# SCH_RemdesKVM_2025-04-20.net
KiCad netlist of a schematic drawn in EasyEDA
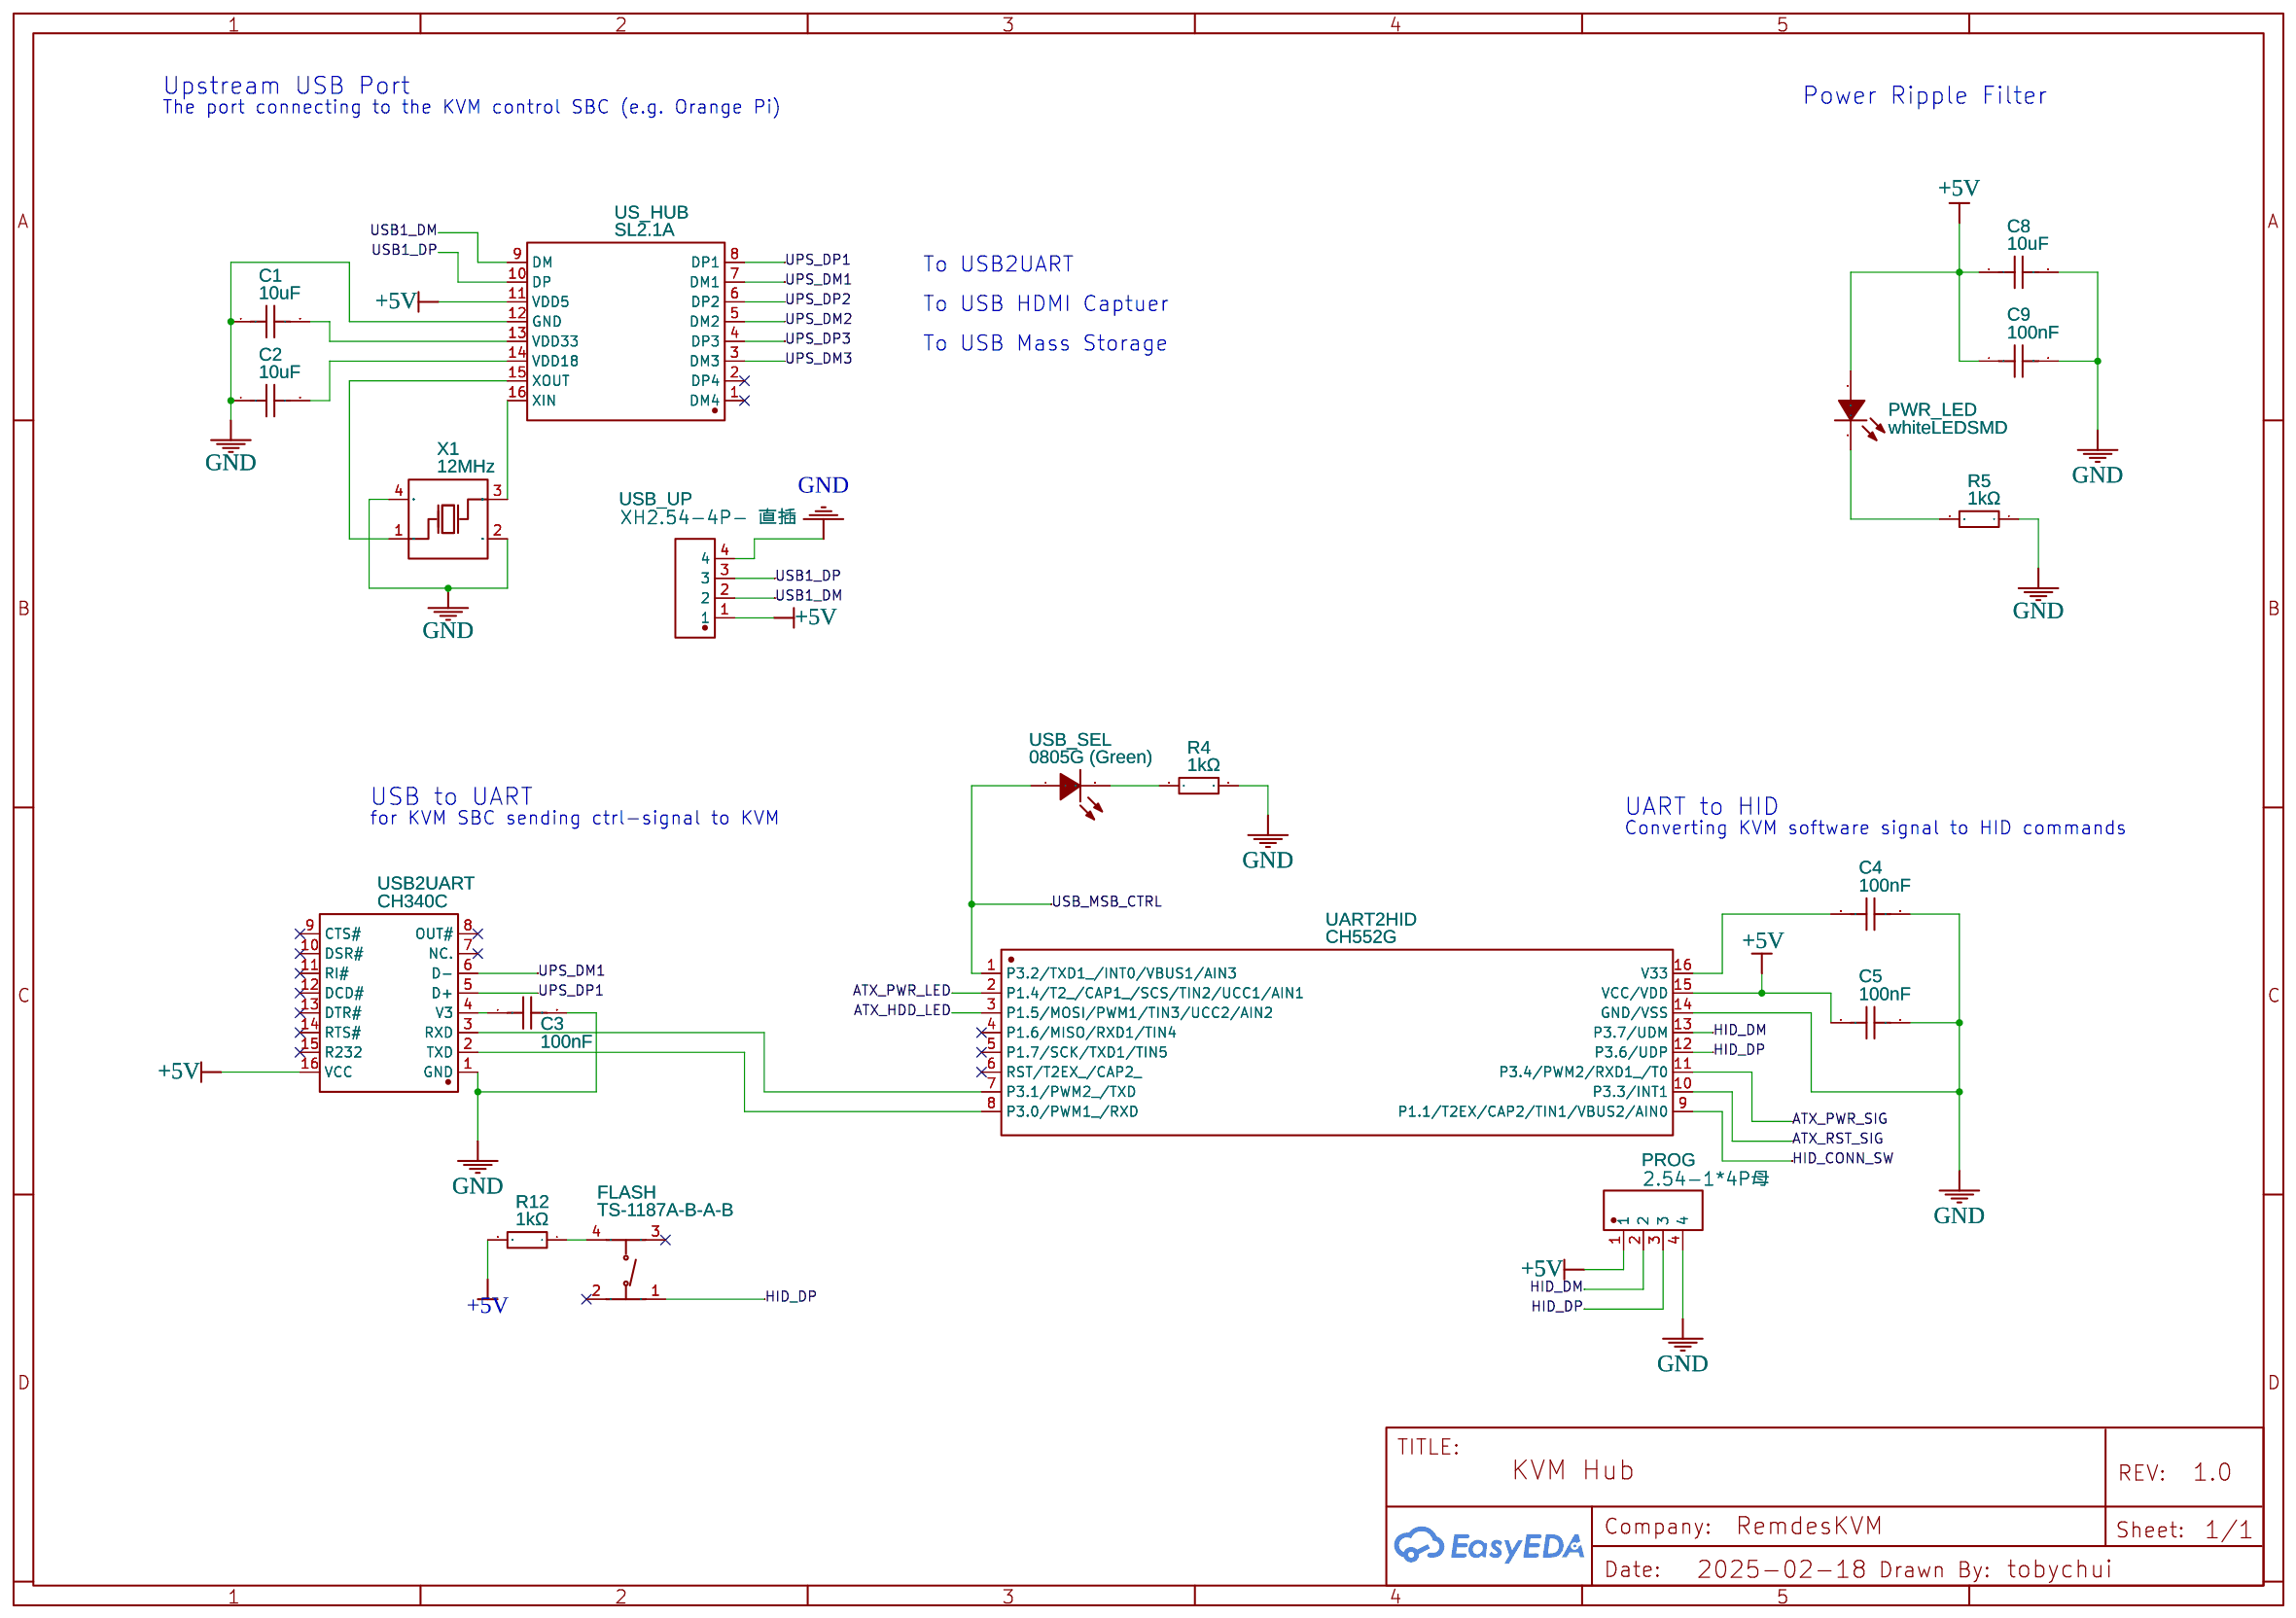
[diagram p0: KVM]
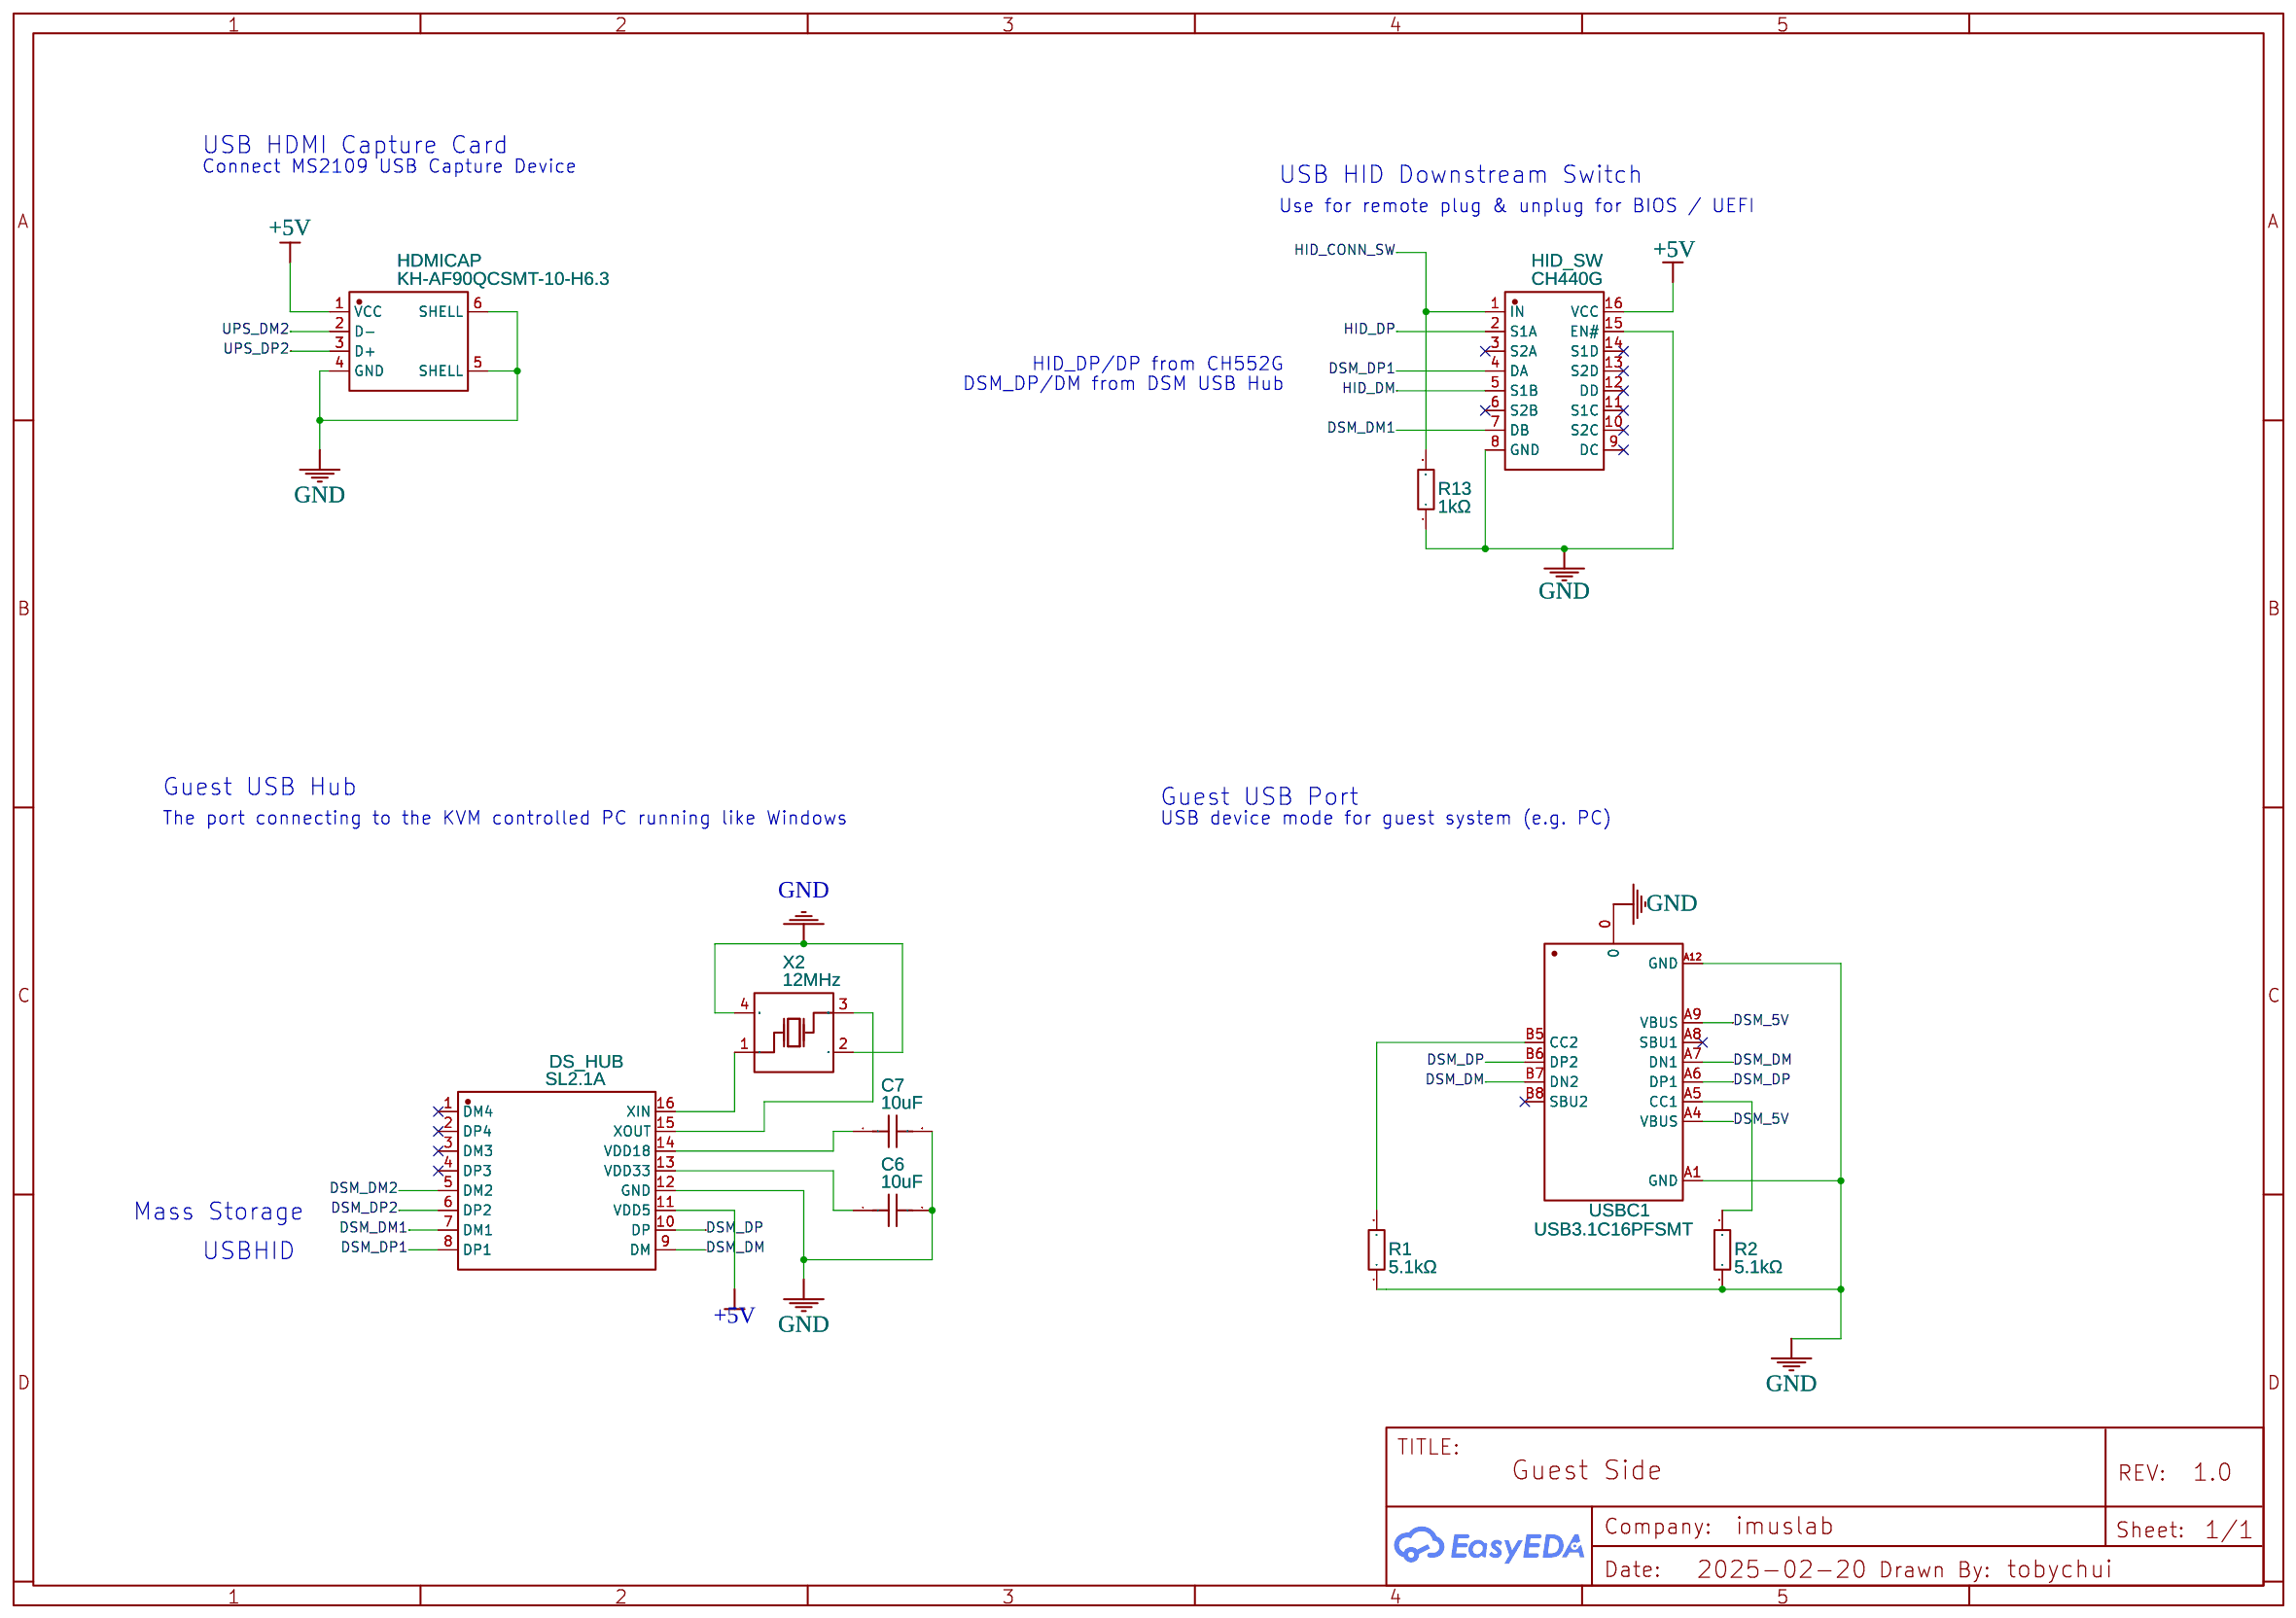
[diagram p1: Guest]
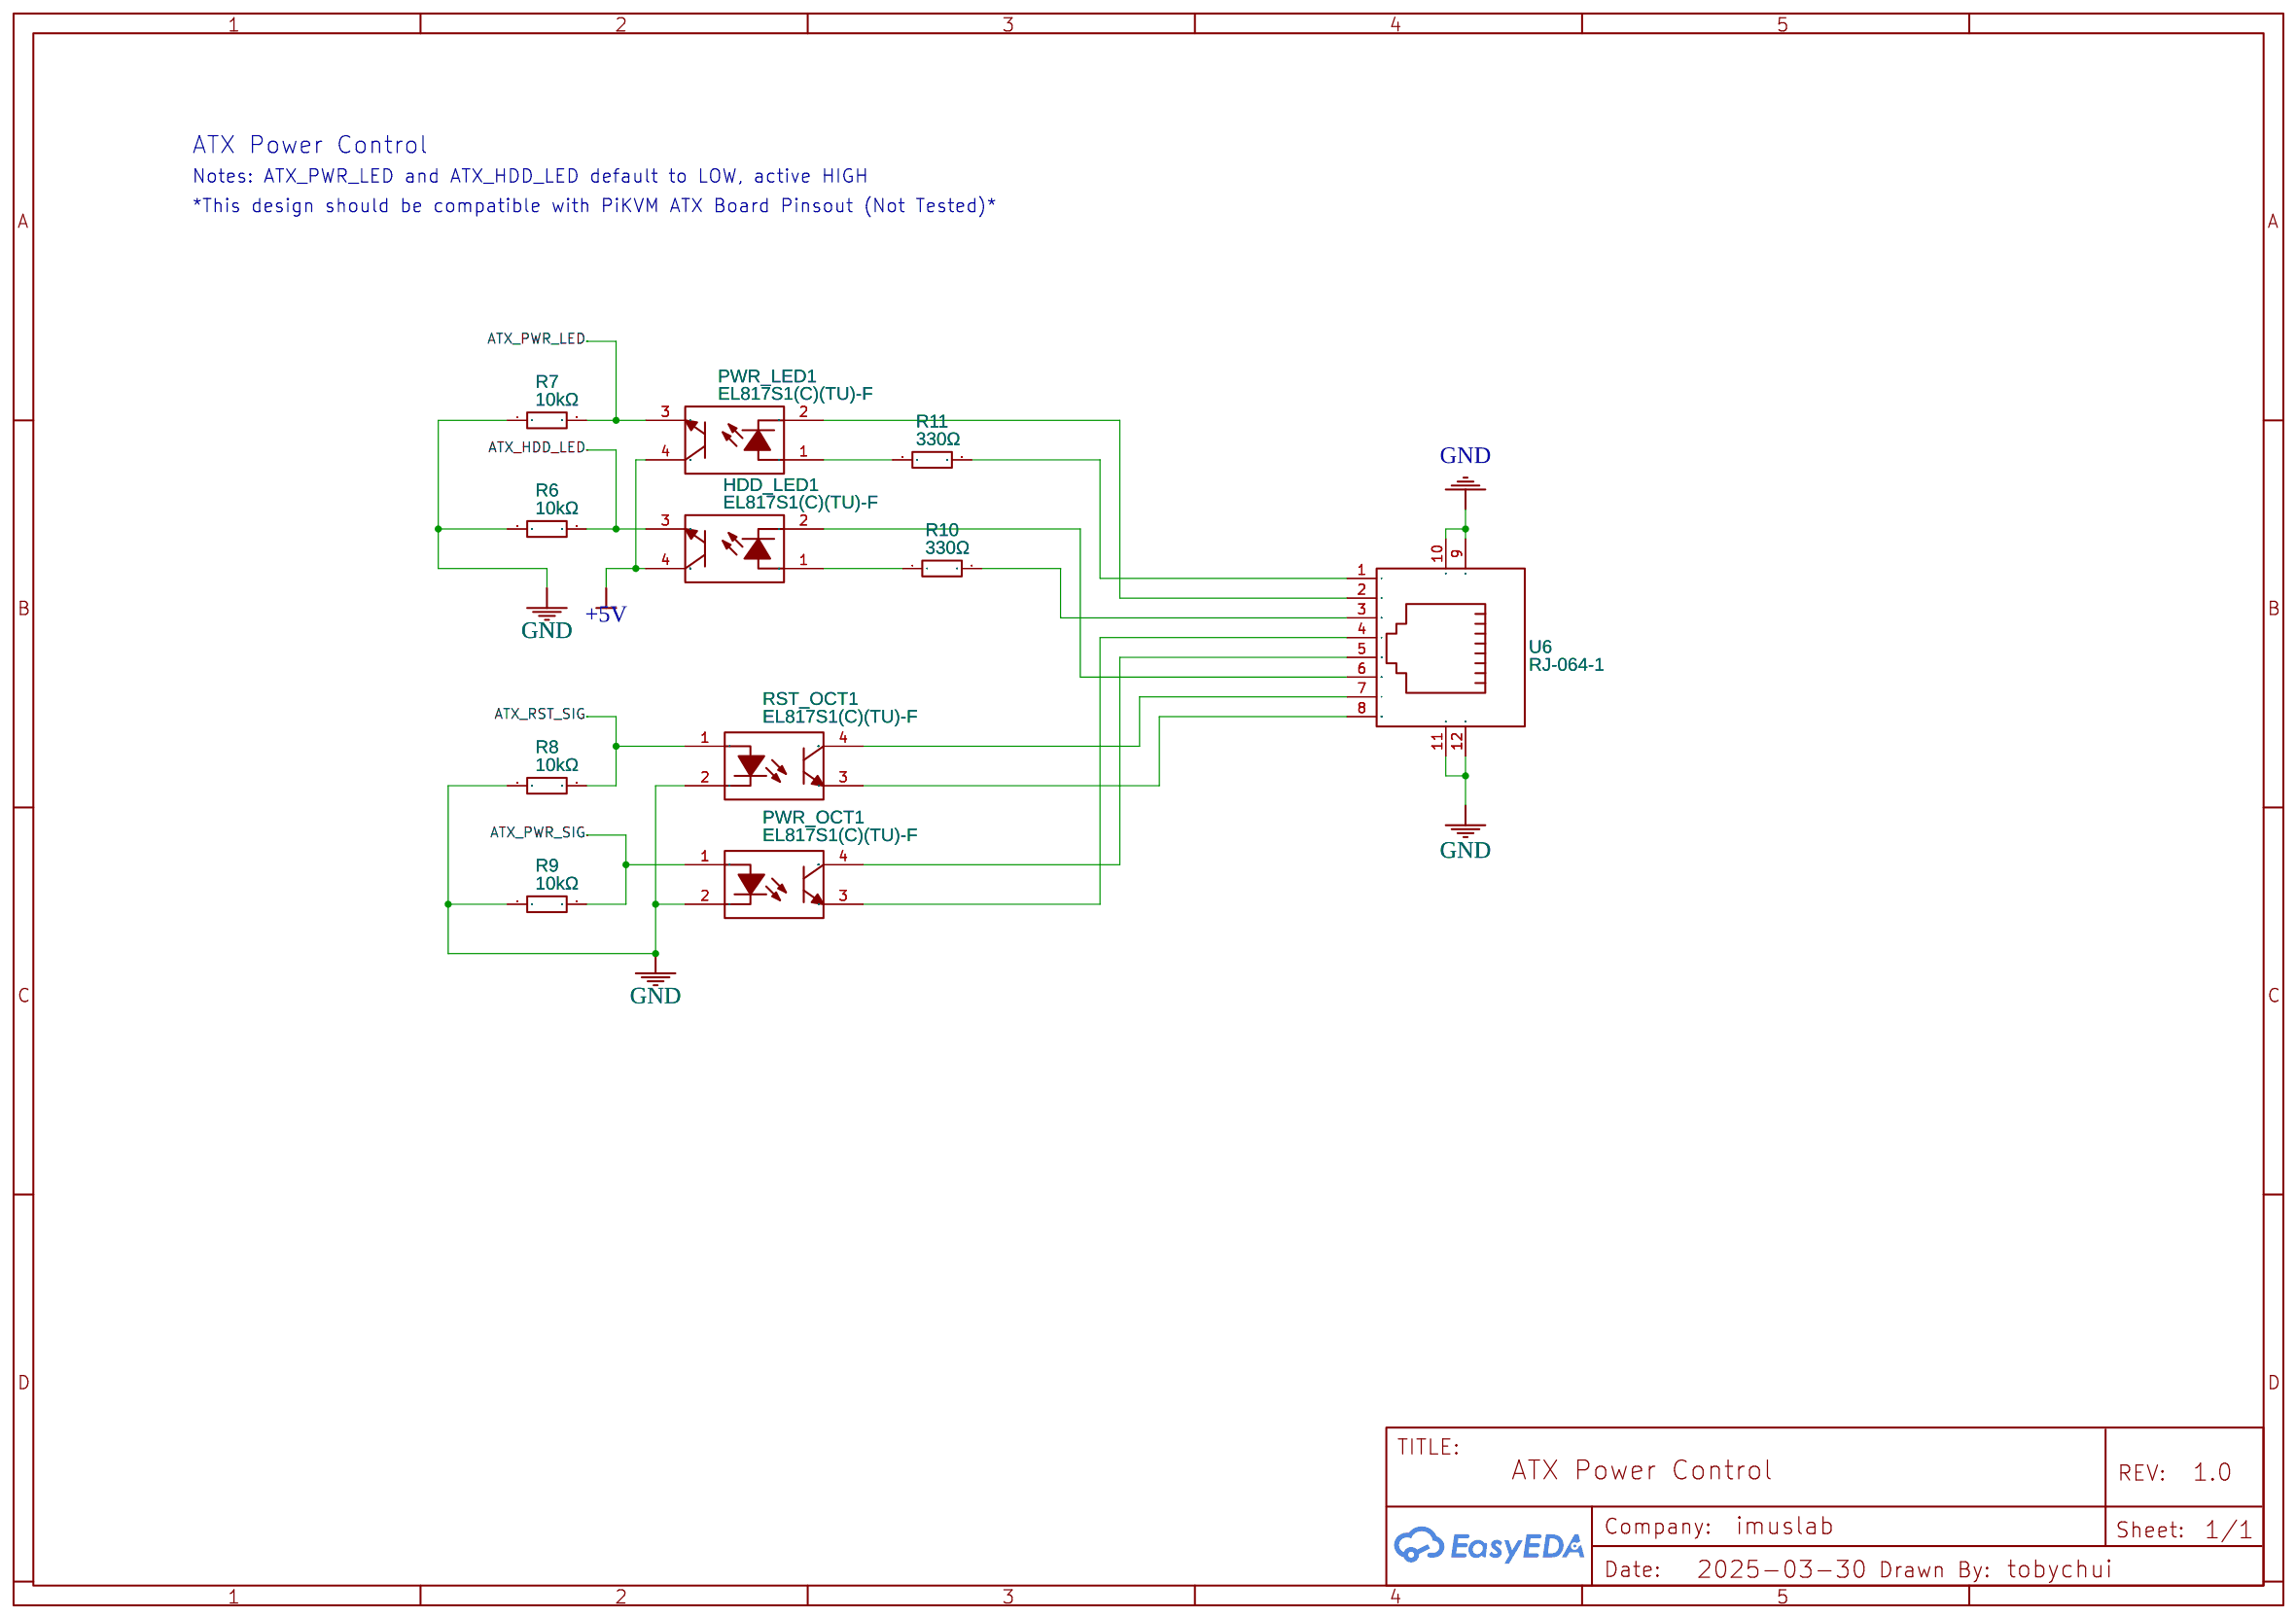
[diagram p2: ATX Power Control]
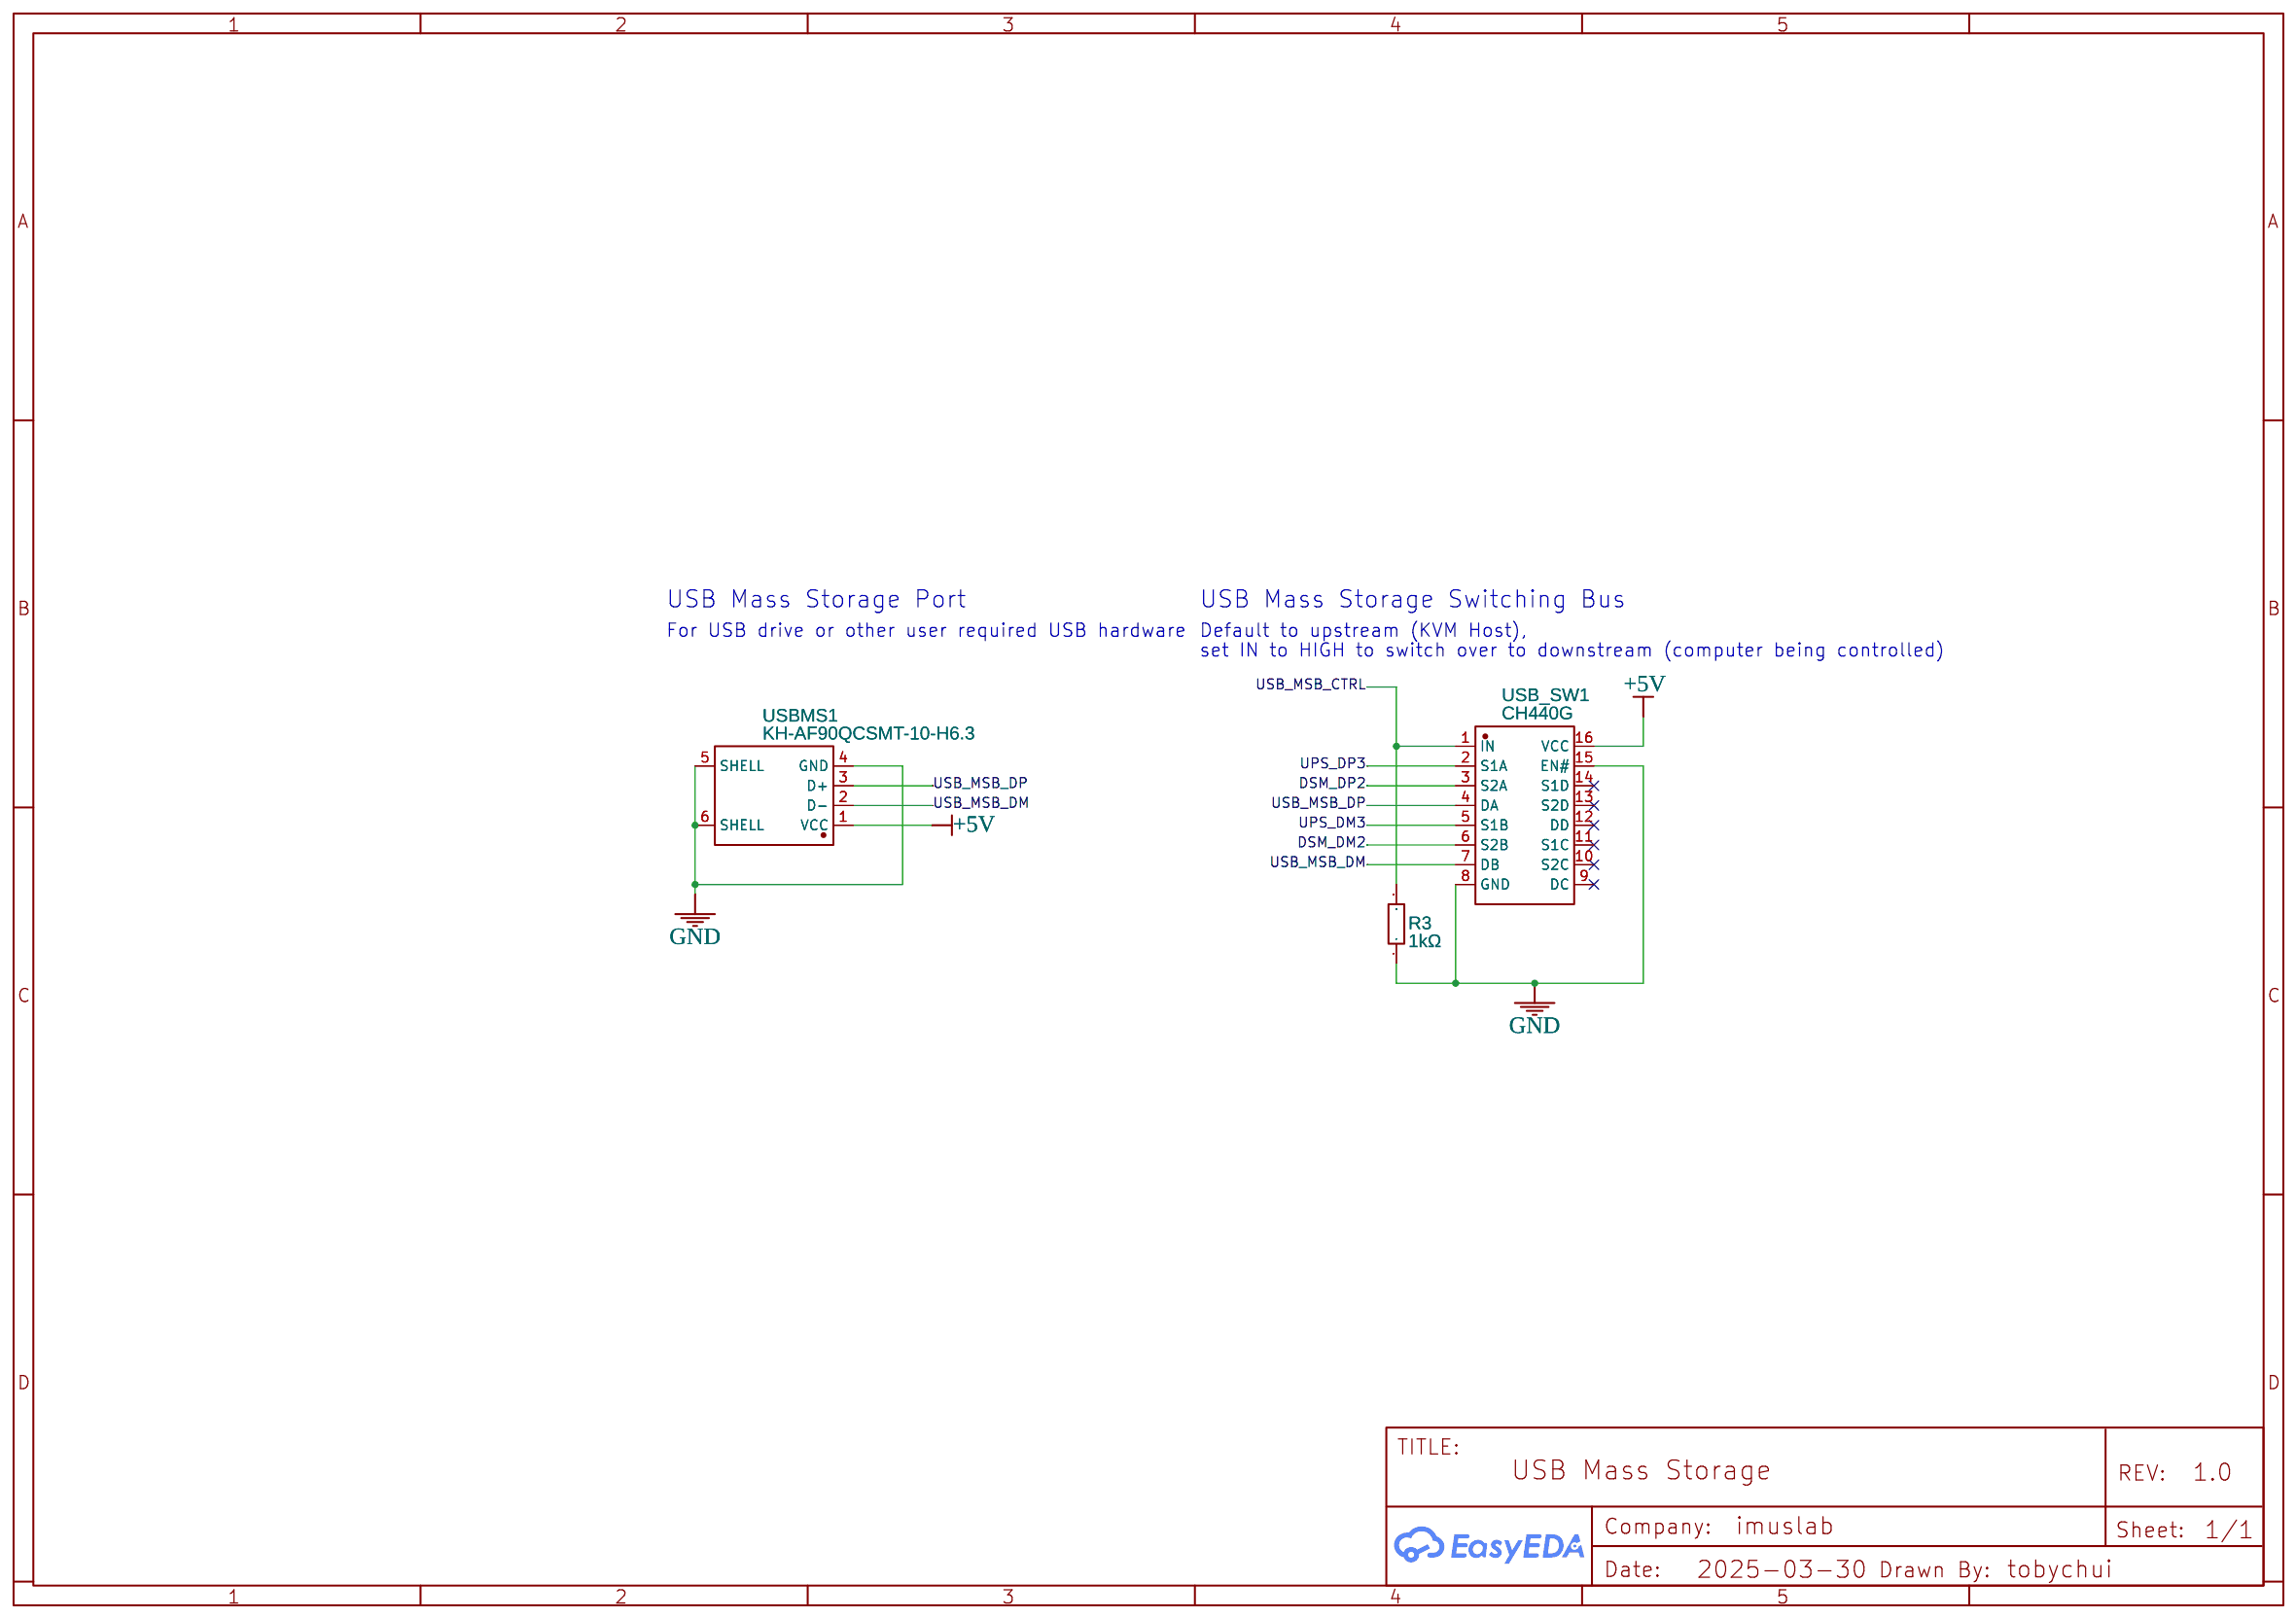
[diagram p3: USB Mass Storage]

(export (version "E")
  (design (tool "Eeschema 10.0.6"))
  (components
    (comp (ref "C1")
      (value "10uF")
      (fields
        (field (name "Manufacturer Part") "CL21A106KAYNNNE")
        (field (name "Manufacturer") "SAMSUNG(三星)")
      )
      (libsource (lib "") (part "CL21A106KAYNNNE"))
    )
    (comp (ref "C2")
      (value "10uF")
      (fields
        (field (name "Manufacturer Part") "CL21A106KAYNNNE")
        (field (name "Manufacturer") "SAMSUNG(三星)")
      )
      (libsource (lib "") (part "CL21A106KAYNNNE"))
    )
    (comp (ref "C3")
      (value "100nF")
      (fields
        (field (name "Manufacturer Part") "CC0805KRX7R9BB104")
        (field (name "Manufacturer") "YAGEO(国巨)")
      )
      (libsource (lib "") (part "CC0805KRX7R9BB104"))
    )
    (comp (ref "C4")
      (value "100nF")
      (fields
        (field (name "Manufacturer Part") "CC0805KRX7R9BB104")
        (field (name "Manufacturer") "YAGEO(国巨)")
      )
      (libsource (lib "") (part "CC0805KRX7R9BB104"))
    )
    (comp (ref "C5")
      (value "100nF")
      (fields
        (field (name "Manufacturer Part") "CC0805KRX7R9BB104")
        (field (name "Manufacturer") "YAGEO(国巨)")
      )
      (libsource (lib "") (part "CC0805KRX7R9BB104"))
    )
    (comp (ref "C8")
      (value "10uF")
      (fields
        (field (name "Manufacturer Part") "CL21A106KAYNNNE")
        (field (name "Manufacturer") "SAMSUNG(三星)")
      )
      (libsource (lib "") (part "CL21A106KAYNNNE"))
    )
    (comp (ref "C9")
      (value "100nF")
      (fields
        (field (name "Manufacturer Part") "CC0805KRX7R9BB104")
        (field (name "Manufacturer") "YAGEO(国巨)")
      )
      (libsource (lib "") (part "CC0805KRX7R9BB104"))
    )
    (comp (ref "FLASH")
      (value "TS-1187A-B-A-B")
      (fields (field (name "Manufacturer") "XKB Connectivity(中国星坤)"))
      (libsource (lib "") (part "TS-1187A-B-A-B"))
    )
    (comp (ref "PROG")
      (value "2.54-1*4P母")
      (fields (field (name "Manufacturer") "BOOMELE(博穆精密)"))
      (libsource (lib "") (part "2.54-1*4P母"))
    )
    (comp (ref "PWR_LED")
      (value "whiteLEDSMD")
      (fields (field (name "Manufacturer Part") "KT-0805W") (field (name "Manufacturer") "KENTO"))
      (libsource (lib "") (part "whiteLEDSMD"))
    )
    (comp (ref "R4")
      (value "1kΩ")
      (fields
        (field (name "Manufacturer Part") "0805W8F1001T5E")
        (field (name "Manufacturer") "UNI-ROYAL(厚声)")
      )
      (libsource (lib "") (part "0805W8F1001T5E"))
    )
    (comp (ref "R5")
      (value "1kΩ")
      (fields
        (field (name "Manufacturer Part") "0805W8F1001T5E")
        (field (name "Manufacturer") "UNI-ROYAL(厚声)")
      )
      (libsource (lib "") (part "0805W8F1001T5E"))
    )
    (comp (ref "R12")
      (value "1kΩ")
      (fields
        (field (name "Manufacturer Part") "0805W8F1001T5E")
        (field (name "Manufacturer") "UNI-ROYAL(厚声)")
      )
      (libsource (lib "") (part "0805W8F1001T5E"))
    )
    (comp (ref "UART2HID")
      (value "CH552G")
      (fields (field (name "Manufacturer") "WCH(南京沁恒)"))
      (libsource (lib "") (part "CH552G"))
    )
    (comp (ref "USB2UART")
      (value "CH340C")
      (fields (field (name "Manufacturer") "WCH(南京沁恒)"))
      (libsource (lib "") (part "CH340C"))
    )
    (comp (ref "USB_SEL")
      (value "0805G (Green)")
      (fields (field (name "Manufacturer Part") "KT-0805G") (field (name "Manufacturer") "KENTO"))
      (libsource (lib "") (part "0805G (Green)"))
    )
    (comp (ref "USB_UP") (value "XH2.54-4P- 直插") (libsource (lib "") (part "XH2.54-4P- 直插")))
    (comp (ref "US_HUB")
      (value "SL2.1A")
      (fields (field (name "Manufacturer") "CoreChips(和芯润德)"))
      (libsource (lib "") (part "SL2.1A"))
    )
    (comp (ref "X1")
      (value "12MHz")
      (fields (field (name "Manufacturer Part") "X322512MSB4SI") (field (name "Manufacturer") "YXC(扬兴晶振)"))
      (libsource (lib "") (part "X322512MSB4SI"))
    )
    (comp (ref "C6")
      (value "10uF")
      (fields
        (field (name "Manufacturer Part") "CL21A106KAYNNNE")
        (field (name "Manufacturer") "SAMSUNG(三星)")
      )
      (libsource (lib "") (part "CL21A106KAYNNNE"))
    )
    (comp (ref "C7")
      (value "10uF")
      (fields
        (field (name "Manufacturer Part") "CL21A106KAYNNNE")
        (field (name "Manufacturer") "SAMSUNG(三星)")
      )
      (libsource (lib "") (part "CL21A106KAYNNNE"))
    )
    (comp (ref "DS_HUB")
      (value "SL2.1A")
      (fields (field (name "Manufacturer") "CoreChips(和芯润德)"))
      (libsource (lib "") (part "SL2.1A"))
    )
    (comp (ref "HDMICAP")
      (value "KH-AF90QCSMT-10-H6.3")
      (fields (field (name "Manufacturer") "kinghelm(金航标)"))
      (libsource (lib "") (part "KH-AF90QCSMT-10-H6.3"))
    )
    (comp (ref "HID_SW")
      (value "CH440G")
      (fields (field (name "Manufacturer") "WCH(南京沁恒)"))
      (libsource (lib "") (part "CH440G"))
    )
    (comp (ref "R1")
      (value "5.1kΩ")
      (fields
        (field (name "Manufacturer Part") "0805W8F5101T5E")
        (field (name "Manufacturer") "UNI-ROYAL(厚声)")
      )
      (libsource (lib "") (part "0805W8F5101T5E"))
    )
    (comp (ref "R2")
      (value "5.1kΩ")
      (fields
        (field (name "Manufacturer Part") "0805W8F5101T5E")
        (field (name "Manufacturer") "UNI-ROYAL(厚声)")
      )
      (libsource (lib "") (part "0805W8F5101T5E"))
    )
    (comp (ref "R13")
      (value "1kΩ")
      (fields
        (field (name "Manufacturer Part") "0805W8F1001T5E")
        (field (name "Manufacturer") "UNI-ROYAL(厚声)")
      )
      (libsource (lib "") (part "0805W8F1001T5E"))
    )
    (comp (ref "USBC1")
      (value "USB3.1C16PFSMT")
      (fields (field (name "Manufacturer Part") "918-418K2023S40001") (field (name "Manufacturer") "精拓金"))
      (libsource (lib "") (part "USB3.1C16PFSMT"))
    )
    (comp (ref "X2")
      (value "12MHz")
      (fields (field (name "Manufacturer Part") "X322512MSB4SI") (field (name "Manufacturer") "YXC(扬兴晶振)"))
      (libsource (lib "") (part "X322512MSB4SI"))
    )
    (comp (ref "HDD_LED1")
      (value "EL817S1(C)(TU)-F")
      (fields (field (name "Manufacturer") "EVERLIGHT(亿光)"))
      (libsource (lib "") (part "EL817S1(C)(TU)-F"))
    )
    (comp (ref "PWR_LED1")
      (value "EL817S1(C)(TU)-F")
      (fields (field (name "Manufacturer") "EVERLIGHT(亿光)"))
      (libsource (lib "") (part "EL817S1(C)(TU)-F_1"))
    )
    (comp (ref "PWR_OCT1")
      (value "EL817S1(C)(TU)-F")
      (fields (field (name "Manufacturer") "EVERLIGHT(亿光)"))
      (libsource (lib "") (part "EL817S1(C)(TU)-F_2"))
    )
    (comp (ref "R6")
      (value "10kΩ")
      (fields
        (field (name "Manufacturer Part") "0805W8F1002T5E")
        (field (name "Manufacturer") "UNI-ROYAL(厚声)")
      )
      (libsource (lib "") (part "0805W8F1002T5E"))
    )
    (comp (ref "R7")
      (value "10kΩ")
      (fields
        (field (name "Manufacturer Part") "0805W8F1002T5E")
        (field (name "Manufacturer") "UNI-ROYAL(厚声)")
      )
      (libsource (lib "") (part "0805W8F1002T5E"))
    )
    (comp (ref "R8")
      (value "10kΩ")
      (fields
        (field (name "Manufacturer Part") "0805W8F1002T5E")
        (field (name "Manufacturer") "UNI-ROYAL(厚声)")
      )
      (libsource (lib "") (part "0805W8F1002T5E"))
    )
    (comp (ref "R9")
      (value "10kΩ")
      (fields
        (field (name "Manufacturer Part") "0805W8F1002T5E")
        (field (name "Manufacturer") "UNI-ROYAL(厚声)")
      )
      (libsource (lib "") (part "0805W8F1002T5E"))
    )
    (comp (ref "R10")
      (value "330Ω")
      (fields
        (field (name "Manufacturer Part") "0805W8F3300T5E")
        (field (name "Manufacturer") "UNI-ROYAL(厚声)")
      )
      (libsource (lib "") (part "0805W8F3300T5E"))
    )
    (comp (ref "R11")
      (value "330Ω")
      (fields
        (field (name "Manufacturer Part") "0805W8F3300T5E")
        (field (name "Manufacturer") "UNI-ROYAL(厚声)")
      )
      (libsource (lib "") (part "0805W8F3300T5E"))
    )
    (comp (ref "RST_OCT1")
      (value "EL817S1(C)(TU)-F")
      (fields (field (name "Manufacturer") "EVERLIGHT(亿光)"))
      (libsource (lib "") (part "EL817S1(C)(TU)-F_3"))
    )
    (comp (ref "U6")
      (value "RJ-064-1")
      (fields (field (name "Manufacturer") "FG(富港)"))
      (libsource (lib "") (part "RJ-064-1"))
    )
    (comp (ref "R3")
      (value "1kΩ")
      (fields
        (field (name "Manufacturer Part") "0805W8F1001T5E")
        (field (name "Manufacturer") "UNI-ROYAL(厚声)")
      )
      (libsource (lib "") (part "0805W8F1001T5E"))
    )
    (comp (ref "USBMS1")
      (value "KH-AF90QCSMT-10-H6.3")
      (fields (field (name "Manufacturer") "kinghelm(金航标)"))
      (libsource (lib "") (part "KH-AF90QCSMT-10-H6.3"))
    )
    (comp (ref "USB_SW1")
      (value "CH440G")
      (fields (field (name "Manufacturer") "WCH(南京沁恒)"))
      (libsource (lib "") (part "CH440G"))
    )
  )
  (nets
    (net (code "1") (name "+5V") (class "Default")
      (node (ref "C5") (pin "1") (pinfunction "1_1") (pintype "unspecified"))
      (node (ref "C8") (pin "1") (pinfunction "1_1") (pintype "unspecified"))
      (node (ref "C9") (pin "1") (pinfunction "1_1") (pintype "unspecified"))
      (node (ref "DS_HUB") (pin "11") (pinfunction "VDD5_11") (pintype "unspecified"))
      (node (ref "HDD_LED1") (pin "4") (pinfunction "COL_4") (pintype "unspecified"))
      (node (ref "HDMICAP") (pin "1") (pinfunction "VCC_1") (pintype "unspecified"))
      (node (ref "HID_SW") (pin "16") (pinfunction "VCC_16") (pintype "unspecified"))
      (node (ref "PROG") (pin "1") (pinfunction "1_1") (pintype "unspecified"))
      (node (ref "PWR_LED") (pin "1") (pinfunction "A_1") (pintype "unspecified"))
      (node (ref "PWR_LED1") (pin "4") (pinfunction "COL_4") (pintype "unspecified"))
      (node (ref "R12") (pin "2") (pinfunction "2_2") (pintype "input"))
      (node (ref "UART2HID") (pin "15") (pinfunction "VCC/VDD_15") (pintype "unspecified"))
      (node (ref "USB2UART") (pin "16") (pinfunction "VCC_16") (pintype "unspecified"))
      (node (ref "USBMS1") (pin "1") (pinfunction "VCC_1") (pintype "unspecified"))
      (node (ref "USB_SW1") (pin "16") (pinfunction "VCC_16") (pintype "unspecified"))
      (node (ref "USB_UP") (pin "1") (pinfunction "1_1") (pintype "unspecified"))
      (node (ref "US_HUB") (pin "11") (pinfunction "VDD5_11") (pintype "unspecified"))
    )
    (net (code "2") (name "ATX_HDD_LED") (class "Default")
      (node (ref "HDD_LED1") (pin "3") (pinfunction "EM_3") (pintype "unspecified"))
      (node (ref "R6") (pin "2") (pinfunction "2_2") (pintype "input"))
      (node (ref "UART2HID") (pin "3") (pinfunction "P1.5/MOSI/PWM1/TIN3/UCC2/AIN2_3") (pintype "unspecified"))
    )
    (net (code "3") (name "ATX_PWR_LED") (class "Default")
      (node (ref "PWR_LED1") (pin "3") (pinfunction "EM_3") (pintype "unspecified"))
      (node (ref "R7") (pin "2") (pinfunction "2_2") (pintype "input"))
      (node (ref "UART2HID") (pin "2") (pinfunction "P1.4/T2_/CAP1_/SCS/TIN2/UCC1/AIN1_2") (pintype "unspecified"))
    )
    (net (code "4") (name "ATX_PWR_SIG") (class "Default")
      (node (ref "PWR_OCT1") (pin "1") (pinfunction "AN_1") (pintype "unspecified"))
      (node (ref "R9") (pin "2") (pinfunction "2_2") (pintype "input"))
      (node (ref "UART2HID") (pin "11") (pinfunction "P3.4/PWM2/RXD1_/T0_11") (pintype "unspecified"))
    )
    (net (code "5") (name "ATX_RST_SIG") (class "Default")
      (node (ref "R8") (pin "2") (pinfunction "2_2") (pintype "input"))
      (node (ref "RST_OCT1") (pin "1") (pinfunction "AN_1") (pintype "unspecified"))
      (node (ref "UART2HID") (pin "10") (pinfunction "P3.3/INT1_10") (pintype "unspecified"))
    )
    (net (code "6") (name "DSM_5V") (class "Default")
      (node (ref "USBC1") (pin "A4") (pinfunction "VBUS_A4") (pintype "unspecified"))
      (node (ref "USBC1") (pin "A9") (pinfunction "VBUS_A9") (pintype "unspecified"))
    )
    (net (code "7") (name "DSM_DM") (class "Default")
      (node (ref "DS_HUB") (pin "9") (pinfunction "DM_9") (pintype "unspecified"))
      (node (ref "USBC1") (pin "A7") (pinfunction "DN1_A7") (pintype "unspecified"))
      (node (ref "USBC1") (pin "B7") (pinfunction "DN2_B7") (pintype "unspecified"))
    )
    (net (code "8") (name "DSM_DM1") (class "Default")
      (node (ref "DS_HUB") (pin "7") (pinfunction "DM1_7") (pintype "unspecified"))
      (node (ref "HID_SW") (pin "7") (pinfunction "DB_7") (pintype "unspecified"))
    )
    (net (code "9") (name "DSM_DM2") (class "Default")
      (node (ref "DS_HUB") (pin "5") (pinfunction "DM2_5") (pintype "unspecified"))
      (node (ref "USB_SW1") (pin "6") (pinfunction "S2B_6") (pintype "unspecified"))
    )
    (net (code "10") (name "DSM_DP") (class "Default")
      (node (ref "DS_HUB") (pin "10") (pinfunction "DP_10") (pintype "unspecified"))
      (node (ref "USBC1") (pin "A6") (pinfunction "DP1_A6") (pintype "unspecified"))
      (node (ref "USBC1") (pin "B6") (pinfunction "DP2_B6") (pintype "unspecified"))
    )
    (net (code "11") (name "DSM_DP1") (class "Default")
      (node (ref "DS_HUB") (pin "8") (pinfunction "DP1_8") (pintype "unspecified"))
      (node (ref "HID_SW") (pin "4") (pinfunction "DA_4") (pintype "unspecified"))
    )
    (net (code "12") (name "DSM_DP2") (class "Default")
      (node (ref "DS_HUB") (pin "6") (pinfunction "DP2_6") (pintype "unspecified"))
      (node (ref "USB_SW1") (pin "3") (pinfunction "S2A_3") (pintype "unspecified"))
    )
    (net (code "13") (name "GND") (class "Default")
      (node (ref "C1") (pin "1") (pinfunction "1_1") (pintype "unspecified"))
      (node (ref "C2") (pin "1") (pinfunction "1_1") (pintype "unspecified"))
      (node (ref "C3") (pin "2") (pinfunction "2_2") (pintype "unspecified"))
      (node (ref "C4") (pin "2") (pinfunction "2_2") (pintype "unspecified"))
      (node (ref "C5") (pin "2") (pinfunction "2_2") (pintype "unspecified"))
      (node (ref "C6") (pin "2") (pinfunction "2_2") (pintype "unspecified"))
      (node (ref "C7") (pin "2") (pinfunction "2_2") (pintype "unspecified"))
      (node (ref "C8") (pin "2") (pinfunction "2_2") (pintype "unspecified"))
      (node (ref "C9") (pin "2") (pinfunction "2_2") (pintype "unspecified"))
      (node (ref "DS_HUB") (pin "12") (pinfunction "GND_12") (pintype "unspecified"))
      (node (ref "HDMICAP") (pin "4") (pinfunction "GND_4") (pintype "unspecified"))
      (node (ref "HDMICAP") (pin "5") (pinfunction "SHELL_5") (pintype "unspecified"))
      (node (ref "HDMICAP") (pin "6") (pinfunction "SHELL_6") (pintype "unspecified"))
      (node (ref "HID_SW") (pin "15") (pinfunction "EN#_15") (pintype "unspecified"))
      (node (ref "HID_SW") (pin "8") (pinfunction "GND_8") (pintype "unspecified"))
      (node (ref "PROG") (pin "4") (pinfunction "4_4") (pintype "unspecified"))
      (node (ref "PWR_OCT1") (pin "2") (pinfunction "CAT_2") (pintype "unspecified"))
      (node (ref "R1") (pin "1") (pinfunction "1_1") (pintype "input"))
      (node (ref "R13") (pin "1") (pinfunction "1_1") (pintype "input"))
      (node (ref "R2") (pin "1") (pinfunction "1_1") (pintype "input"))
      (node (ref "R3") (pin "1") (pinfunction "1_1") (pintype "input"))
      (node (ref "R4") (pin "1") (pinfunction "1_1") (pintype "input"))
      (node (ref "R5") (pin "1") (pinfunction "1_1") (pintype "input"))
      (node (ref "R6") (pin "1") (pinfunction "1_1") (pintype "input"))
      (node (ref "R7") (pin "1") (pinfunction "1_1") (pintype "input"))
      (node (ref "R8") (pin "1") (pinfunction "1_1") (pintype "input"))
      (node (ref "R9") (pin "1") (pinfunction "1_1") (pintype "input"))
      (node (ref "RST_OCT1") (pin "2") (pinfunction "CAT_2") (pintype "unspecified"))
      (node (ref "U6") (pin "10") (pinfunction "EH_10") (pintype "unspecified"))
      (node (ref "U6") (pin "11") (pinfunction "EH_11") (pintype "unspecified"))
      (node (ref "U6") (pin "12") (pinfunction "EH_12") (pintype "unspecified"))
      (node (ref "U6") (pin "9") (pinfunction "EH_9") (pintype "unspecified"))
      (node (ref "UART2HID") (pin "14") (pinfunction "GND/VSS_14") (pintype "unspecified"))
      (node (ref "USB2UART") (pin "1") (pinfunction "GND_1") (pintype "unspecified"))
      (node (ref "USBC1") (pin "0") (pinfunction "0_0") (pintype "unspecified"))
      (node (ref "USBC1") (pin "A1") (pinfunction "GND_A1") (pintype "unspecified"))
      (node (ref "USBC1") (pin "A12") (pinfunction "GND_A12") (pintype "unspecified"))
      (node (ref "USBMS1") (pin "4") (pinfunction "GND_4") (pintype "unspecified"))
      (node (ref "USBMS1") (pin "5") (pinfunction "SHELL_5") (pintype "unspecified"))
      (node (ref "USBMS1") (pin "6") (pinfunction "SHELL_6") (pintype "unspecified"))
      (node (ref "USB_SW1") (pin "15") (pinfunction "EN#_15") (pintype "unspecified"))
      (node (ref "USB_SW1") (pin "8") (pinfunction "GND_8") (pintype "unspecified"))
      (node (ref "USB_UP") (pin "4") (pinfunction "4_4") (pintype "unspecified"))
      (node (ref "US_HUB") (pin "12") (pinfunction "GND_12") (pintype "unspecified"))
      (node (ref "X1") (pin "2") (pinfunction "GND_2") (pintype "unspecified"))
      (node (ref "X1") (pin "4") (pinfunction "GND_4") (pintype "unspecified"))
      (node (ref "X2") (pin "2") (pinfunction "GND_2") (pintype "unspecified"))
      (node (ref "X2") (pin "4") (pinfunction "GND_4") (pintype "unspecified"))
    )
    (net (code "14") (name "HID_CONN_SW") (class "Default")
      (node (ref "HID_SW") (pin "1") (pinfunction "IN_1") (pintype "unspecified"))
      (node (ref "R13") (pin "2") (pinfunction "2_2") (pintype "input"))
      (node (ref "UART2HID") (pin "9") (pinfunction "P1.1/T2EX/CAP2/TIN1/VBUS2/AIN0_9") (pintype "unspecified"))
    )
    (net (code "15") (name "HID_DM") (class "Default")
      (node (ref "HID_SW") (pin "5") (pinfunction "S1B_5") (pintype "unspecified"))
      (node (ref "PROG") (pin "2") (pinfunction "2_2") (pintype "unspecified"))
      (node (ref "UART2HID") (pin "13") (pinfunction "P3.7/UDM_13") (pintype "unspecified"))
    )
    (net (code "16") (name "HID_DP") (class "Default")
      (node (ref "FLASH") (pin "1") (pinfunction "A_1") (pintype "unspecified"))
      (node (ref "HID_SW") (pin "2") (pinfunction "S1A_2") (pintype "unspecified"))
      (node (ref "PROG") (pin "3") (pinfunction "3_3") (pintype "unspecified"))
      (node (ref "UART2HID") (pin "12") (pinfunction "P3.6/UDP_12") (pintype "unspecified"))
    )
    (net (code "17") (name "Net-(DS_HUB-VDD18)") (class "Default")
      (node (ref "C7") (pin "1") (pinfunction "1_1") (pintype "unspecified"))
      (node (ref "DS_HUB") (pin "14") (pinfunction "VDD18_14") (pintype "unspecified"))
    )
    (net (code "18") (name "Net-(DS_HUB-VDD33)") (class "Default")
      (node (ref "C6") (pin "1") (pinfunction "1_1") (pintype "unspecified"))
      (node (ref "DS_HUB") (pin "13") (pinfunction "VDD33_13") (pintype "unspecified"))
    )
    (net (code "19") (name "Net-(DS_HUB-XIN)") (class "Default")
      (node (ref "DS_HUB") (pin "16") (pinfunction "XIN_16") (pintype "unspecified"))
      (node (ref "X2") (pin "1") (pinfunction "OSC1_1") (pintype "unspecified"))
    )
    (net (code "20") (name "Net-(DS_HUB-XOUT)") (class "Default")
      (node (ref "DS_HUB") (pin "15") (pinfunction "XOUT_15") (pintype "unspecified"))
      (node (ref "X2") (pin "3") (pinfunction "OSC2_3") (pintype "unspecified"))
    )
    (net (code "21") (name "Net-(FLASH-D)") (class "Default")
      (node (ref "FLASH") (pin "4") (pinfunction "D_4") (pintype "unspecified"))
      (node (ref "R12") (pin "1") (pinfunction "1_1") (pintype "input"))
    )
    (net (code "22") (name "Net-(HDD_LED1-AN)") (class "Default")
      (node (ref "HDD_LED1") (pin "1") (pinfunction "AN_1") (pintype "unspecified"))
      (node (ref "R10") (pin "1") (pinfunction "1_1") (pintype "input"))
    )
    (net (code "23") (name "Net-(HDD_LED1-CAT)") (class "Default")
      (node (ref "HDD_LED1") (pin "2") (pinfunction "CAT_2") (pintype "unspecified"))
      (node (ref "U6") (pin "6") (pinfunction "6_6") (pintype "unspecified"))
    )
    (net (code "24") (name "Net-(PWR_LED-K)") (class "Default")
      (node (ref "PWR_LED") (pin "2") (pinfunction "K_2") (pintype "unspecified"))
      (node (ref "R5") (pin "2") (pinfunction "2_2") (pintype "input"))
    )
    (net (code "25") (name "Net-(PWR_LED1-AN)") (class "Default")
      (node (ref "PWR_LED1") (pin "1") (pinfunction "AN_1") (pintype "unspecified"))
      (node (ref "R11") (pin "1") (pinfunction "1_1") (pintype "input"))
    )
    (net (code "26") (name "Net-(PWR_LED1-CAT)") (class "Default")
      (node (ref "PWR_LED1") (pin "2") (pinfunction "CAT_2") (pintype "unspecified"))
      (node (ref "U6") (pin "2") (pinfunction "2_2") (pintype "unspecified"))
    )
    (net (code "27") (name "Net-(PWR_OCT1-COL)") (class "Default")
      (node (ref "PWR_OCT1") (pin "4") (pinfunction "COL_4") (pintype "unspecified"))
      (node (ref "U6") (pin "5") (pinfunction "5_5") (pintype "unspecified"))
    )
    (net (code "28") (name "Net-(PWR_OCT1-EM)") (class "Default")
      (node (ref "PWR_OCT1") (pin "3") (pinfunction "EM_3") (pintype "unspecified"))
      (node (ref "U6") (pin "4") (pinfunction "4_4") (pintype "unspecified"))
    )
    (net (code "29") (name "Net-(R10-Pad2)") (class "Default")
      (node (ref "R10") (pin "2") (pinfunction "2_2") (pintype "input"))
      (node (ref "U6") (pin "3") (pinfunction "3_3") (pintype "unspecified"))
    )
    (net (code "30") (name "Net-(R11-Pad2)") (class "Default")
      (node (ref "R11") (pin "2") (pinfunction "2_2") (pintype "input"))
      (node (ref "U6") (pin "1") (pinfunction "1_1") (pintype "unspecified"))
    )
    (net (code "31") (name "Net-(RST_OCT1-COL)") (class "Default")
      (node (ref "RST_OCT1") (pin "4") (pinfunction "COL_4") (pintype "unspecified"))
      (node (ref "U6") (pin "7") (pinfunction "7_7") (pintype "unspecified"))
    )
    (net (code "32") (name "Net-(RST_OCT1-EM)") (class "Default")
      (node (ref "RST_OCT1") (pin "3") (pinfunction "EM_3") (pintype "unspecified"))
      (node (ref "U6") (pin "8") (pinfunction "8_8") (pintype "unspecified"))
    )
    (net (code "33") (name "Net-(UART2HID-P3.0{slash}PWM1_{slash}RXD)") (class "Default")
      (node (ref "UART2HID") (pin "8") (pinfunction "P3.0/PWM1_/RXD_8") (pintype "unspecified"))
      (node (ref "USB2UART") (pin "2") (pinfunction "TXD_2") (pintype "unspecified"))
    )
    (net (code "34") (name "Net-(UART2HID-P3.1{slash}PWM2_{slash}TXD)") (class "Default")
      (node (ref "UART2HID") (pin "7") (pinfunction "P3.1/PWM2_/TXD_7") (pintype "unspecified"))
      (node (ref "USB2UART") (pin "3") (pinfunction "RXD_3") (pintype "unspecified"))
    )
    (net (code "35") (name "Net-(UART2HID-V33)") (class "Default")
      (node (ref "C4") (pin "1") (pinfunction "1_1") (pintype "unspecified"))
      (node (ref "UART2HID") (pin "16") (pinfunction "V33_16") (pintype "unspecified"))
    )
    (net (code "36") (name "Net-(USB2UART-V3)") (class "Default")
      (node (ref "C3") (pin "1") (pinfunction "1_1") (pintype "unspecified"))
      (node (ref "USB2UART") (pin "4") (pinfunction "V3_4") (pintype "unspecified"))
    )
    (net (code "37") (name "Net-(USBC1-CC1)") (class "Default")
      (node (ref "R2") (pin "2") (pinfunction "2_2") (pintype "input"))
      (node (ref "USBC1") (pin "A5") (pinfunction "CC1_A5") (pintype "unspecified"))
    )
    (net (code "38") (name "Net-(USBC1-CC2)") (class "Default")
      (node (ref "R1") (pin "2") (pinfunction "2_2") (pintype "input"))
      (node (ref "USBC1") (pin "B5") (pinfunction "CC2_B5") (pintype "unspecified"))
    )
    (net (code "39") (name "Net-(USB_SEL-K)") (class "Default")
      (node (ref "R4") (pin "2") (pinfunction "2_2") (pintype "input"))
      (node (ref "USB_SEL") (pin "2") (pinfunction "K_2") (pintype "unspecified"))
    )
    (net (code "40") (name "Net-(US_HUB-VDD18)") (class "Default")
      (node (ref "C2") (pin "2") (pinfunction "2_2") (pintype "unspecified"))
      (node (ref "US_HUB") (pin "14") (pinfunction "VDD18_14") (pintype "unspecified"))
    )
    (net (code "41") (name "Net-(US_HUB-VDD33)") (class "Default")
      (node (ref "C1") (pin "2") (pinfunction "2_2") (pintype "unspecified"))
      (node (ref "US_HUB") (pin "13") (pinfunction "VDD33_13") (pintype "unspecified"))
    )
    (net (code "42") (name "Net-(US_HUB-XIN)") (class "Default")
      (node (ref "US_HUB") (pin "16") (pinfunction "XIN_16") (pintype "unspecified"))
      (node (ref "X1") (pin "3") (pinfunction "OSC2_3") (pintype "unspecified"))
    )
    (net (code "43") (name "Net-(US_HUB-XOUT)") (class "Default")
      (node (ref "US_HUB") (pin "15") (pinfunction "XOUT_15") (pintype "unspecified"))
      (node (ref "X1") (pin "1") (pinfunction "OSC1_1") (pintype "unspecified"))
    )
    (net (code "44") (name "UPS_DM1") (class "Default")
      (node (ref "USB2UART") (pin "6") (pinfunction "D-_6") (pintype "unspecified"))
      (node (ref "US_HUB") (pin "7") (pinfunction "DM1_7") (pintype "unspecified"))
    )
    (net (code "45") (name "UPS_DM2") (class "Default")
      (node (ref "HDMICAP") (pin "2") (pinfunction "D-_2") (pintype "unspecified"))
      (node (ref "US_HUB") (pin "5") (pinfunction "DM2_5") (pintype "unspecified"))
    )
    (net (code "46") (name "UPS_DM3") (class "Default")
      (node (ref "USB_SW1") (pin "5") (pinfunction "S1B_5") (pintype "unspecified"))
      (node (ref "US_HUB") (pin "3") (pinfunction "DM3_3") (pintype "unspecified"))
    )
    (net (code "47") (name "UPS_DP1") (class "Default")
      (node (ref "USB2UART") (pin "5") (pinfunction "D+_5") (pintype "unspecified"))
      (node (ref "US_HUB") (pin "8") (pinfunction "DP1_8") (pintype "unspecified"))
    )
    (net (code "48") (name "UPS_DP2") (class "Default")
      (node (ref "HDMICAP") (pin "3") (pinfunction "D+_3") (pintype "unspecified"))
      (node (ref "US_HUB") (pin "6") (pinfunction "DP2_6") (pintype "unspecified"))
    )
    (net (code "49") (name "UPS_DP3") (class "Default")
      (node (ref "USB_SW1") (pin "2") (pinfunction "S1A_2") (pintype "unspecified"))
      (node (ref "US_HUB") (pin "4") (pinfunction "DP3_4") (pintype "unspecified"))
    )
    (net (code "50") (name "USB1_DM") (class "Default")
      (node (ref "USB_UP") (pin "2") (pinfunction "2_2") (pintype "unspecified"))
      (node (ref "US_HUB") (pin "9") (pinfunction "DM_9") (pintype "unspecified"))
    )
    (net (code "51") (name "USB1_DP") (class "Default")
      (node (ref "USB_UP") (pin "3") (pinfunction "3_3") (pintype "unspecified"))
      (node (ref "US_HUB") (pin "10") (pinfunction "DP_10") (pintype "unspecified"))
    )
    (net (code "52") (name "USB_MSB_CTRL") (class "Default")
      (node (ref "R3") (pin "2") (pinfunction "2_2") (pintype "input"))
      (node (ref "UART2HID") (pin "1") (pinfunction "P3.2/TXD1_/INT0/VBUS1/AIN3_1") (pintype "unspecified"))
      (node (ref "USB_SEL") (pin "1") (pinfunction "A_1") (pintype "unspecified"))
      (node (ref "USB_SW1") (pin "1") (pinfunction "IN_1") (pintype "unspecified"))
    )
    (net (code "53") (name "USB_MSB_DM") (class "Default")
      (node (ref "USBMS1") (pin "2") (pinfunction "D-_2") (pintype "unspecified"))
      (node (ref "USB_SW1") (pin "7") (pinfunction "DB_7") (pintype "unspecified"))
    )
    (net (code "54") (name "USB_MSB_DP") (class "Default")
      (node (ref "USBMS1") (pin "3") (pinfunction "D+_3") (pintype "unspecified"))
      (node (ref "USB_SW1") (pin "4") (pinfunction "DA_4") (pintype "unspecified"))
    )
    (net (code "55") (name "unconnected-(DS_HUB-DM3-Pad3)") (class "Default")
      (node (ref "DS_HUB") (pin "3") (pinfunction "DM3_3") (pintype "unspecified+no_connect"))
    )
    (net (code "56") (name "unconnected-(DS_HUB-DM4-Pad1)") (class "Default")
      (node (ref "DS_HUB") (pin "1") (pinfunction "DM4_1") (pintype "unspecified+no_connect"))
    )
    (net (code "57") (name "unconnected-(DS_HUB-DP3-Pad4)") (class "Default")
      (node (ref "DS_HUB") (pin "4") (pinfunction "DP3_4") (pintype "unspecified+no_connect"))
    )
    (net (code "58") (name "unconnected-(DS_HUB-DP4-Pad2)") (class "Default")
      (node (ref "DS_HUB") (pin "2") (pinfunction "DP4_2") (pintype "unspecified+no_connect"))
    )
    (net (code "59") (name "unconnected-(FLASH-B-Pad2)") (class "Default")
      (node (ref "FLASH") (pin "2") (pinfunction "B_2") (pintype "unspecified+no_connect"))
    )
    (net (code "60") (name "unconnected-(FLASH-C-Pad3)") (class "Default")
      (node (ref "FLASH") (pin "3") (pinfunction "C_3") (pintype "unspecified+no_connect"))
    )
    (net (code "61") (name "unconnected-(HID_SW-DC-Pad9)") (class "Default")
      (node (ref "HID_SW") (pin "9") (pinfunction "DC_9") (pintype "unspecified+no_connect"))
    )
    (net (code "62") (name "unconnected-(HID_SW-DD-Pad12)") (class "Default")
      (node (ref "HID_SW") (pin "12") (pinfunction "DD_12") (pintype "unspecified+no_connect"))
    )
    (net (code "63") (name "unconnected-(HID_SW-S1C-Pad11)") (class "Default")
      (node (ref "HID_SW") (pin "11") (pinfunction "S1C_11") (pintype "unspecified+no_connect"))
    )
    (net (code "64") (name "unconnected-(HID_SW-S1D-Pad14)") (class "Default")
      (node (ref "HID_SW") (pin "14") (pinfunction "S1D_14") (pintype "unspecified+no_connect"))
    )
    (net (code "65") (name "unconnected-(HID_SW-S2A-Pad3)") (class "Default")
      (node (ref "HID_SW") (pin "3") (pinfunction "S2A_3") (pintype "unspecified+no_connect"))
    )
    (net (code "66") (name "unconnected-(HID_SW-S2B-Pad6)") (class "Default")
      (node (ref "HID_SW") (pin "6") (pinfunction "S2B_6") (pintype "unspecified+no_connect"))
    )
    (net (code "67") (name "unconnected-(HID_SW-S2C-Pad10)") (class "Default")
      (node (ref "HID_SW") (pin "10") (pinfunction "S2C_10") (pintype "unspecified+no_connect"))
    )
    (net (code "68") (name "unconnected-(HID_SW-S2D-Pad13)") (class "Default")
      (node (ref "HID_SW") (pin "13") (pinfunction "S2D_13") (pintype "unspecified+no_connect"))
    )
    (net (code "69") (name "unconnected-(UART2HID-P1.6{slash}MISO{slash}RXD1{slash}TIN4-Pad4)") (class "Default")
      (node (ref "UART2HID") (pin "4") (pinfunction "P1.6/MISO/RXD1/TIN4_4") (pintype "unspecified+no_connect"))
    )
    (net (code "70") (name "unconnected-(UART2HID-P1.7{slash}SCK{slash}TXD1{slash}TIN5-Pad5)") (class "Default")
      (node (ref "UART2HID") (pin "5") (pinfunction "P1.7/SCK/TXD1/TIN5_5") (pintype "unspecified+no_connect"))
    )
    (net (code "71") (name "unconnected-(UART2HID-RST{slash}T2EX_{slash}CAP2_-Pad6)") (class "Default")
      (node (ref "UART2HID") (pin "6") (pinfunction "RST/T2EX_/CAP2__6") (pintype "unspecified+no_connect"))
    )
    (net (code "72") (name "unconnected-(USB2UART-CTS#-Pad9)") (class "Default")
      (node (ref "USB2UART") (pin "9") (pinfunction "CTS#_9") (pintype "unspecified+no_connect"))
    )
    (net (code "73") (name "unconnected-(USB2UART-DCD#-Pad12)") (class "Default")
      (node (ref "USB2UART") (pin "12") (pinfunction "DCD#_12") (pintype "unspecified+no_connect"))
    )
    (net (code "74") (name "unconnected-(USB2UART-DSR#-Pad10)") (class "Default")
      (node (ref "USB2UART") (pin "10") (pinfunction "DSR#_10") (pintype "unspecified+no_connect"))
    )
    (net (code "75") (name "unconnected-(USB2UART-DTR#-Pad13)") (class "Default")
      (node (ref "USB2UART") (pin "13") (pinfunction "DTR#_13") (pintype "unspecified+no_connect"))
    )
    (net (code "76") (name "unconnected-(USB2UART-NC.-Pad7)") (class "Default")
      (node (ref "USB2UART") (pin "7") (pinfunction "NC._7") (pintype "unspecified+no_connect"))
    )
    (net (code "77") (name "unconnected-(USB2UART-OUT#-Pad8)") (class "Default")
      (node (ref "USB2UART") (pin "8") (pinfunction "OUT#_8") (pintype "unspecified+no_connect"))
    )
    (net (code "78") (name "unconnected-(USB2UART-R232-Pad15)") (class "Default")
      (node (ref "USB2UART") (pin "15") (pinfunction "R232_15") (pintype "unspecified+no_connect"))
    )
    (net (code "79") (name "unconnected-(USB2UART-RI#-Pad11)") (class "Default")
      (node (ref "USB2UART") (pin "11") (pinfunction "RI#_11") (pintype "unspecified+no_connect"))
    )
    (net (code "80") (name "unconnected-(USB2UART-RTS#-Pad14)") (class "Default")
      (node (ref "USB2UART") (pin "14") (pinfunction "RTS#_14") (pintype "unspecified+no_connect"))
    )
    (net (code "81") (name "unconnected-(USBC1-SBU1-PadA8)") (class "Default")
      (node (ref "USBC1") (pin "A8") (pinfunction "SBU1_A8") (pintype "unspecified+no_connect"))
    )
    (net (code "82") (name "unconnected-(USBC1-SBU2-PadB8)") (class "Default")
      (node (ref "USBC1") (pin "B8") (pinfunction "SBU2_B8") (pintype "unspecified+no_connect"))
    )
    (net (code "83") (name "unconnected-(USB_SW1-DC-Pad9)") (class "Default")
      (node (ref "USB_SW1") (pin "9") (pinfunction "DC_9") (pintype "unspecified+no_connect"))
    )
    (net (code "84") (name "unconnected-(USB_SW1-DD-Pad12)") (class "Default")
      (node (ref "USB_SW1") (pin "12") (pinfunction "DD_12") (pintype "unspecified+no_connect"))
    )
    (net (code "85") (name "unconnected-(USB_SW1-S1C-Pad11)") (class "Default")
      (node (ref "USB_SW1") (pin "11") (pinfunction "S1C_11") (pintype "unspecified+no_connect"))
    )
    (net (code "86") (name "unconnected-(USB_SW1-S1D-Pad14)") (class "Default")
      (node (ref "USB_SW1") (pin "14") (pinfunction "S1D_14") (pintype "unspecified+no_connect"))
    )
    (net (code "87") (name "unconnected-(USB_SW1-S2C-Pad10)") (class "Default")
      (node (ref "USB_SW1") (pin "10") (pinfunction "S2C_10") (pintype "unspecified+no_connect"))
    )
    (net (code "88") (name "unconnected-(USB_SW1-S2D-Pad13)") (class "Default")
      (node (ref "USB_SW1") (pin "13") (pinfunction "S2D_13") (pintype "unspecified+no_connect"))
    )
    (net (code "89") (name "unconnected-(US_HUB-DM4-Pad1)") (class "Default")
      (node (ref "US_HUB") (pin "1") (pinfunction "DM4_1") (pintype "unspecified+no_connect"))
    )
    (net (code "90") (name "unconnected-(US_HUB-DP4-Pad2)") (class "Default")
      (node (ref "US_HUB") (pin "2") (pinfunction "DP4_2") (pintype "unspecified+no_connect"))
    )
  )
)
